# rotary_breakout.net
KiCad netlist of a schematic drawn in EAGLE
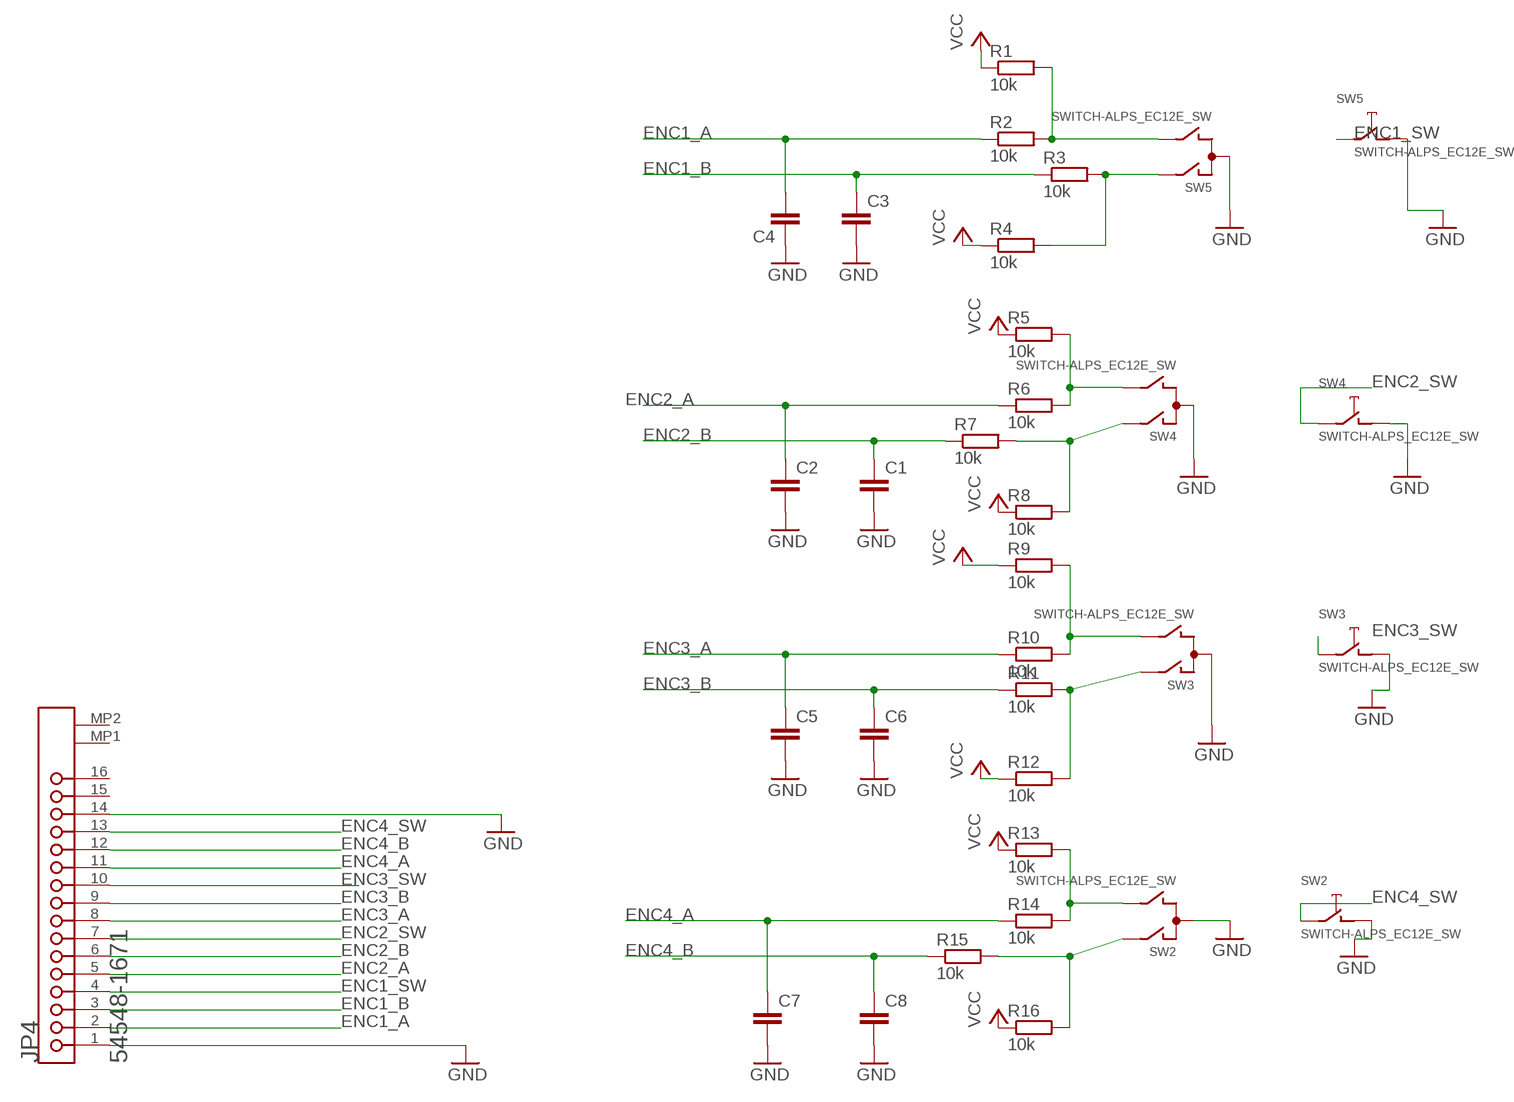
[diagram p0: schematic, sheet 1]

(export (version "E")
  (design (tool "Eeschema 10.0.6"))
  (components
    (comp (ref "C1")
      (value "C-EUC0805")
      (footprint "eagle-import:C0805")
      (libsource (lib "eagle-import") (part "C-EUC0805"))
    )
    (comp (ref "C2")
      (value "C-EUC0805")
      (footprint "eagle-import:C0805")
      (libsource (lib "eagle-import") (part "C-EUC0805"))
    )
    (comp (ref "C3")
      (value "C-EUC0805")
      (footprint "eagle-import:C0805")
      (libsource (lib "eagle-import") (part "C-EUC0805"))
    )
    (comp (ref "C4")
      (value "C-EUC0805")
      (footprint "eagle-import:C0805")
      (libsource (lib "eagle-import") (part "C-EUC0805"))
    )
    (comp (ref "C5")
      (value "C-EUC0805")
      (footprint "eagle-import:C0805")
      (libsource (lib "eagle-import") (part "C-EUC0805"))
    )
    (comp (ref "C6")
      (value "C-EUC0805")
      (footprint "eagle-import:C0805")
      (libsource (lib "eagle-import") (part "C-EUC0805"))
    )
    (comp (ref "C7")
      (value "C-EUC0805")
      (footprint "eagle-import:C0805")
      (libsource (lib "eagle-import") (part "C-EUC0805"))
    )
    (comp (ref "C8")
      (value "C-EUC0805")
      (footprint "eagle-import:C0805")
      (libsource (lib "eagle-import") (part "C-EUC0805"))
    )
    (comp (ref "JP4")
      (value "MOLEX_54548-1671MOLEX_54548-1671_0_0")
      (footprint "eagle-import:MOLEX_54548-1671_0")
      (fields (field (name "MF") "Molex") (field (name "MPN") "54548-1671"))
      (libsource (lib "eagle-import") (part "MOLEX_54548-1671MOLEX_54548-1671_0_0"))
    )
    (comp (ref "R1")
      (value "10k")
      (footprint "eagle-import:R0603")
      (libsource (lib "eagle-import") (part "R-EU_R0603"))
    )
    (comp (ref "R2")
      (value "10k")
      (footprint "eagle-import:R0603")
      (libsource (lib "eagle-import") (part "R-EU_R0603"))
    )
    (comp (ref "R3")
      (value "10k")
      (footprint "eagle-import:R0603")
      (libsource (lib "eagle-import") (part "R-EU_R0603"))
    )
    (comp (ref "R4")
      (value "10k")
      (footprint "eagle-import:R0603")
      (libsource (lib "eagle-import") (part "R-EU_R0603"))
    )
    (comp (ref "R5")
      (value "10k")
      (footprint "eagle-import:R0603")
      (libsource (lib "eagle-import") (part "R-EU_R0603"))
    )
    (comp (ref "R6")
      (value "10k")
      (footprint "eagle-import:R0603")
      (libsource (lib "eagle-import") (part "R-EU_R0603"))
    )
    (comp (ref "R7")
      (value "10k")
      (footprint "eagle-import:R0603")
      (libsource (lib "eagle-import") (part "R-EU_R0603"))
    )
    (comp (ref "R8")
      (value "10k")
      (footprint "eagle-import:R0603")
      (libsource (lib "eagle-import") (part "R-EU_R0603"))
    )
    (comp (ref "R9")
      (value "10k")
      (footprint "eagle-import:R0603")
      (libsource (lib "eagle-import") (part "R-EU_R0603"))
    )
    (comp (ref "R10")
      (value "10k")
      (footprint "eagle-import:R0603")
      (libsource (lib "eagle-import") (part "R-EU_R0603"))
    )
    (comp (ref "R11")
      (value "10k")
      (footprint "eagle-import:R0603")
      (libsource (lib "eagle-import") (part "R-EU_R0603"))
    )
    (comp (ref "R12")
      (value "10k")
      (footprint "eagle-import:R0603")
      (libsource (lib "eagle-import") (part "R-EU_R0603"))
    )
    (comp (ref "R13")
      (value "10k")
      (footprint "eagle-import:R0603")
      (libsource (lib "eagle-import") (part "R-EU_R0603"))
    )
    (comp (ref "R14")
      (value "10k")
      (footprint "eagle-import:R0603")
      (libsource (lib "eagle-import") (part "R-EU_R0603"))
    )
    (comp (ref "R15")
      (value "10k")
      (footprint "eagle-import:R0603")
      (libsource (lib "eagle-import") (part "R-EU_R0603"))
    )
    (comp (ref "R16")
      (value "10k")
      (footprint "eagle-import:R0603")
      (libsource (lib "eagle-import") (part "R-EU_R0603"))
    )
    (comp (ref "SW2")
      (value "SWITCH-ALPS_EC12E_SW")
      (footprint "eagle-import:SWITCH-ALPS_ALPS_EC12E_SW")
      (fields (field (name "MPN") "EC12E2424407"))
      (libsource (lib "eagle-import") (part "SWITCH-ALPS_EC12E_SW"))
    )
    (comp (ref "SW3")
      (value "SWITCH-ALPS_EC12E_SW")
      (footprint "eagle-import:SWITCH-ALPS_ALPS_EC12E_SW")
      (fields (field (name "MPN") "EC12E2424407"))
      (libsource (lib "eagle-import") (part "SWITCH-ALPS_EC12E_SW"))
    )
    (comp (ref "SW4")
      (value "SWITCH-ALPS_EC12E_SW")
      (footprint "eagle-import:SWITCH-ALPS_ALPS_EC12E_SW")
      (fields (field (name "MPN") "EC12E2424407"))
      (libsource (lib "eagle-import") (part "SWITCH-ALPS_EC12E_SW"))
    )
    (comp (ref "SW5")
      (value "SWITCH-ALPS_EC12E_SW")
      (footprint "eagle-import:SWITCH-ALPS_ALPS_EC12E_SW")
      (fields (field (name "MPN") "EC12E2424407"))
      (libsource (lib "eagle-import") (part "SWITCH-ALPS_EC12E_SW"))
    )
  )
  (nets
    (net (code "1") (name "/ENC1_A") (class "Default")
      (node (ref "C4") (pin "2") (pinfunction "2_2") (pintype "passive"))
      (node (ref "JP4") (pin "2") (pinfunction "2_2") (pintype "passive"))
      (node (ref "R2") (pin "1") (pinfunction "1_1") (pintype "passive"))
    )
    (net (code "2") (name "/ENC1_B") (class "Default")
      (node (ref "C3") (pin "1") (pinfunction "1_1") (pintype "passive"))
      (node (ref "JP4") (pin "3") (pinfunction "3_3") (pintype "passive"))
      (node (ref "R3") (pin "1") (pinfunction "1_1") (pintype "passive"))
    )
    (net (code "3") (name "/ENC1_SW") (class "Default")
      (node (ref "JP4") (pin "4") (pinfunction "4_4") (pintype "passive"))
      (node (ref "SW5") (pin "E") (pinfunction "2_E") (pintype "passive"))
    )
    (net (code "4") (name "/ENC2_A") (class "Default")
      (node (ref "C2") (pin "1") (pinfunction "1_1") (pintype "passive"))
      (node (ref "JP4") (pin "5") (pinfunction "5_5") (pintype "passive"))
      (node (ref "R6") (pin "1") (pinfunction "1_1") (pintype "passive"))
    )
    (net (code "5") (name "/ENC2_B") (class "Default")
      (node (ref "C1") (pin "1") (pinfunction "1_1") (pintype "passive"))
      (node (ref "JP4") (pin "6") (pinfunction "6_6") (pintype "passive"))
      (node (ref "R7") (pin "1") (pinfunction "1_1") (pintype "passive"))
    )
    (net (code "6") (name "/ENC2_SW") (class "Default")
      (node (ref "JP4") (pin "7") (pinfunction "7_7") (pintype "passive"))
      (node (ref "SW4") (pin "E") (pinfunction "2_E") (pintype "passive"))
    )
    (net (code "7") (name "/ENC3_A") (class "Default")
      (node (ref "C5") (pin "1") (pinfunction "1_1") (pintype "passive"))
      (node (ref "JP4") (pin "8") (pinfunction "8_8") (pintype "passive"))
      (node (ref "R10") (pin "1") (pinfunction "1_1") (pintype "passive"))
    )
    (net (code "8") (name "/ENC3_B") (class "Default")
      (node (ref "C6") (pin "1") (pinfunction "1_1") (pintype "passive"))
      (node (ref "JP4") (pin "9") (pinfunction "9_9") (pintype "passive"))
      (node (ref "R11") (pin "1") (pinfunction "1_1") (pintype "passive"))
    )
    (net (code "9") (name "/ENC3_SW") (class "Default")
      (node (ref "JP4") (pin "10") (pinfunction "10_10") (pintype "passive"))
      (node (ref "SW3") (pin "E") (pinfunction "2_E") (pintype "passive"))
    )
    (net (code "10") (name "/ENC4_A") (class "Default")
      (node (ref "C7") (pin "1") (pinfunction "1_1") (pintype "passive"))
      (node (ref "JP4") (pin "11") (pinfunction "11_11") (pintype "passive"))
      (node (ref "R14") (pin "1") (pinfunction "1_1") (pintype "passive"))
    )
    (net (code "11") (name "/ENC4_B") (class "Default")
      (node (ref "C8") (pin "1") (pinfunction "1_1") (pintype "passive"))
      (node (ref "JP4") (pin "12") (pinfunction "12_12") (pintype "passive"))
      (node (ref "R15") (pin "1") (pinfunction "1_1") (pintype "passive"))
    )
    (net (code "12") (name "/ENC4_SW") (class "Default")
      (node (ref "JP4") (pin "13") (pinfunction "13_13") (pintype "passive"))
      (node (ref "SW2") (pin "E") (pinfunction "2_E") (pintype "passive"))
    )
    (net (code "13") (name "GND") (class "Default")
      (node (ref "C1") (pin "2") (pinfunction "2_2") (pintype "passive"))
      (node (ref "C2") (pin "2") (pinfunction "2_2") (pintype "passive"))
      (node (ref "C3") (pin "2") (pinfunction "2_2") (pintype "passive"))
      (node (ref "C4") (pin "1") (pinfunction "1_1") (pintype "passive"))
      (node (ref "C5") (pin "2") (pinfunction "2_2") (pintype "passive"))
      (node (ref "C6") (pin "2") (pinfunction "2_2") (pintype "passive"))
      (node (ref "C7") (pin "2") (pinfunction "2_2") (pintype "passive"))
      (node (ref "C8") (pin "2") (pinfunction "2_2") (pintype "passive"))
      (node (ref "JP4") (pin "1") (pinfunction "1_1") (pintype "passive"))
      (node (ref "JP4") (pin "14") (pinfunction "14_14") (pintype "passive"))
      (node (ref "SW2") (pin "C") (pinfunction "C_C") (pintype "passive"))
      (node (ref "SW2") (pin "D") (pinfunction "1_D") (pintype "passive"))
      (node (ref "SW3") (pin "C") (pinfunction "C_C") (pintype "passive"))
      (node (ref "SW3") (pin "D") (pinfunction "1_D") (pintype "passive"))
      (node (ref "SW4") (pin "C") (pinfunction "C_C") (pintype "passive"))
      (node (ref "SW4") (pin "D") (pinfunction "1_D") (pintype "passive"))
      (node (ref "SW5") (pin "C") (pinfunction "C_C") (pintype "passive"))
      (node (ref "SW5") (pin "D") (pinfunction "1_D") (pintype "passive"))
    )
    (net (code "14") (name "Net-(R1-Pad2)") (class "Default")
      (node (ref "R1") (pin "2") (pinfunction "2_2") (pintype "passive"))
      (node (ref "R2") (pin "2") (pinfunction "2_2") (pintype "passive"))
      (node (ref "SW5") (pin "B") (pinfunction "B_B") (pintype "passive"))
    )
    (net (code "15") (name "Net-(R3-Pad2)") (class "Default")
      (node (ref "R3") (pin "2") (pinfunction "2_2") (pintype "passive"))
      (node (ref "R4") (pin "2") (pinfunction "2_2") (pintype "passive"))
      (node (ref "SW5") (pin "A") (pinfunction "A_A") (pintype "passive"))
    )
    (net (code "16") (name "Net-(R5-Pad2)") (class "Default")
      (node (ref "R5") (pin "2") (pinfunction "2_2") (pintype "passive"))
      (node (ref "R6") (pin "2") (pinfunction "2_2") (pintype "passive"))
      (node (ref "SW4") (pin "B") (pinfunction "B_B") (pintype "passive"))
    )
    (net (code "17") (name "Net-(R7-Pad2)") (class "Default")
      (node (ref "R7") (pin "2") (pinfunction "2_2") (pintype "passive"))
      (node (ref "R8") (pin "2") (pinfunction "2_2") (pintype "passive"))
      (node (ref "SW4") (pin "A") (pinfunction "A_A") (pintype "passive"))
    )
    (net (code "18") (name "Net-(R10-Pad2)") (class "Default")
      (node (ref "R10") (pin "2") (pinfunction "2_2") (pintype "passive"))
      (node (ref "R9") (pin "2") (pinfunction "2_2") (pintype "passive"))
      (node (ref "SW3") (pin "B") (pinfunction "B_B") (pintype "passive"))
    )
    (net (code "19") (name "Net-(R11-Pad2)") (class "Default")
      (node (ref "R11") (pin "2") (pinfunction "2_2") (pintype "passive"))
      (node (ref "R12") (pin "2") (pinfunction "2_2") (pintype "passive"))
      (node (ref "SW3") (pin "A") (pinfunction "A_A") (pintype "passive"))
    )
    (net (code "20") (name "Net-(R13-Pad2)") (class "Default")
      (node (ref "R13") (pin "2") (pinfunction "2_2") (pintype "passive"))
      (node (ref "R14") (pin "2") (pinfunction "2_2") (pintype "passive"))
      (node (ref "SW2") (pin "B") (pinfunction "B_B") (pintype "passive"))
    )
    (net (code "21") (name "Net-(R15-Pad2)") (class "Default")
      (node (ref "R15") (pin "2") (pinfunction "2_2") (pintype "passive"))
      (node (ref "R16") (pin "2") (pinfunction "2_2") (pintype "passive"))
      (node (ref "SW2") (pin "A") (pinfunction "A_A") (pintype "passive"))
    )
    (net (code "22") (name "VCC") (class "Default")
      (node (ref "R1") (pin "1") (pinfunction "1_1") (pintype "passive"))
      (node (ref "R12") (pin "1") (pinfunction "1_1") (pintype "passive"))
      (node (ref "R13") (pin "1") (pinfunction "1_1") (pintype "passive"))
      (node (ref "R16") (pin "1") (pinfunction "1_1") (pintype "passive"))
      (node (ref "R4") (pin "1") (pinfunction "1_1") (pintype "passive"))
      (node (ref "R5") (pin "1") (pinfunction "1_1") (pintype "passive"))
      (node (ref "R8") (pin "1") (pinfunction "1_1") (pintype "passive"))
      (node (ref "R9") (pin "1") (pinfunction "1_1") (pintype "passive"))
    )
    (net (code "23") (name "unconnected-(JP4-Pad15)") (class "Default")
      (node (ref "JP4") (pin "15") (pinfunction "15_15") (pintype "passive"))
    )
    (net (code "24") (name "unconnected-(JP4-Pad16)") (class "Default")
      (node (ref "JP4") (pin "16") (pinfunction "16_16") (pintype "passive"))
    )
    (net (code "25") (name "unconnected-(JP4-PadMP1)") (class "Default")
      (node (ref "JP4") (pin "MP1") (pinfunction "MP1_MP1") (pintype "passive"))
    )
    (net (code "26") (name "unconnected-(JP4-PadMP2)") (class "Default")
      (node (ref "JP4") (pin "MP2") (pinfunction "MP2_MP2") (pintype "passive"))
    )
  )
)
